# POWER_1_1.net
KiCad netlist of a schematic drawn in Altium Designer
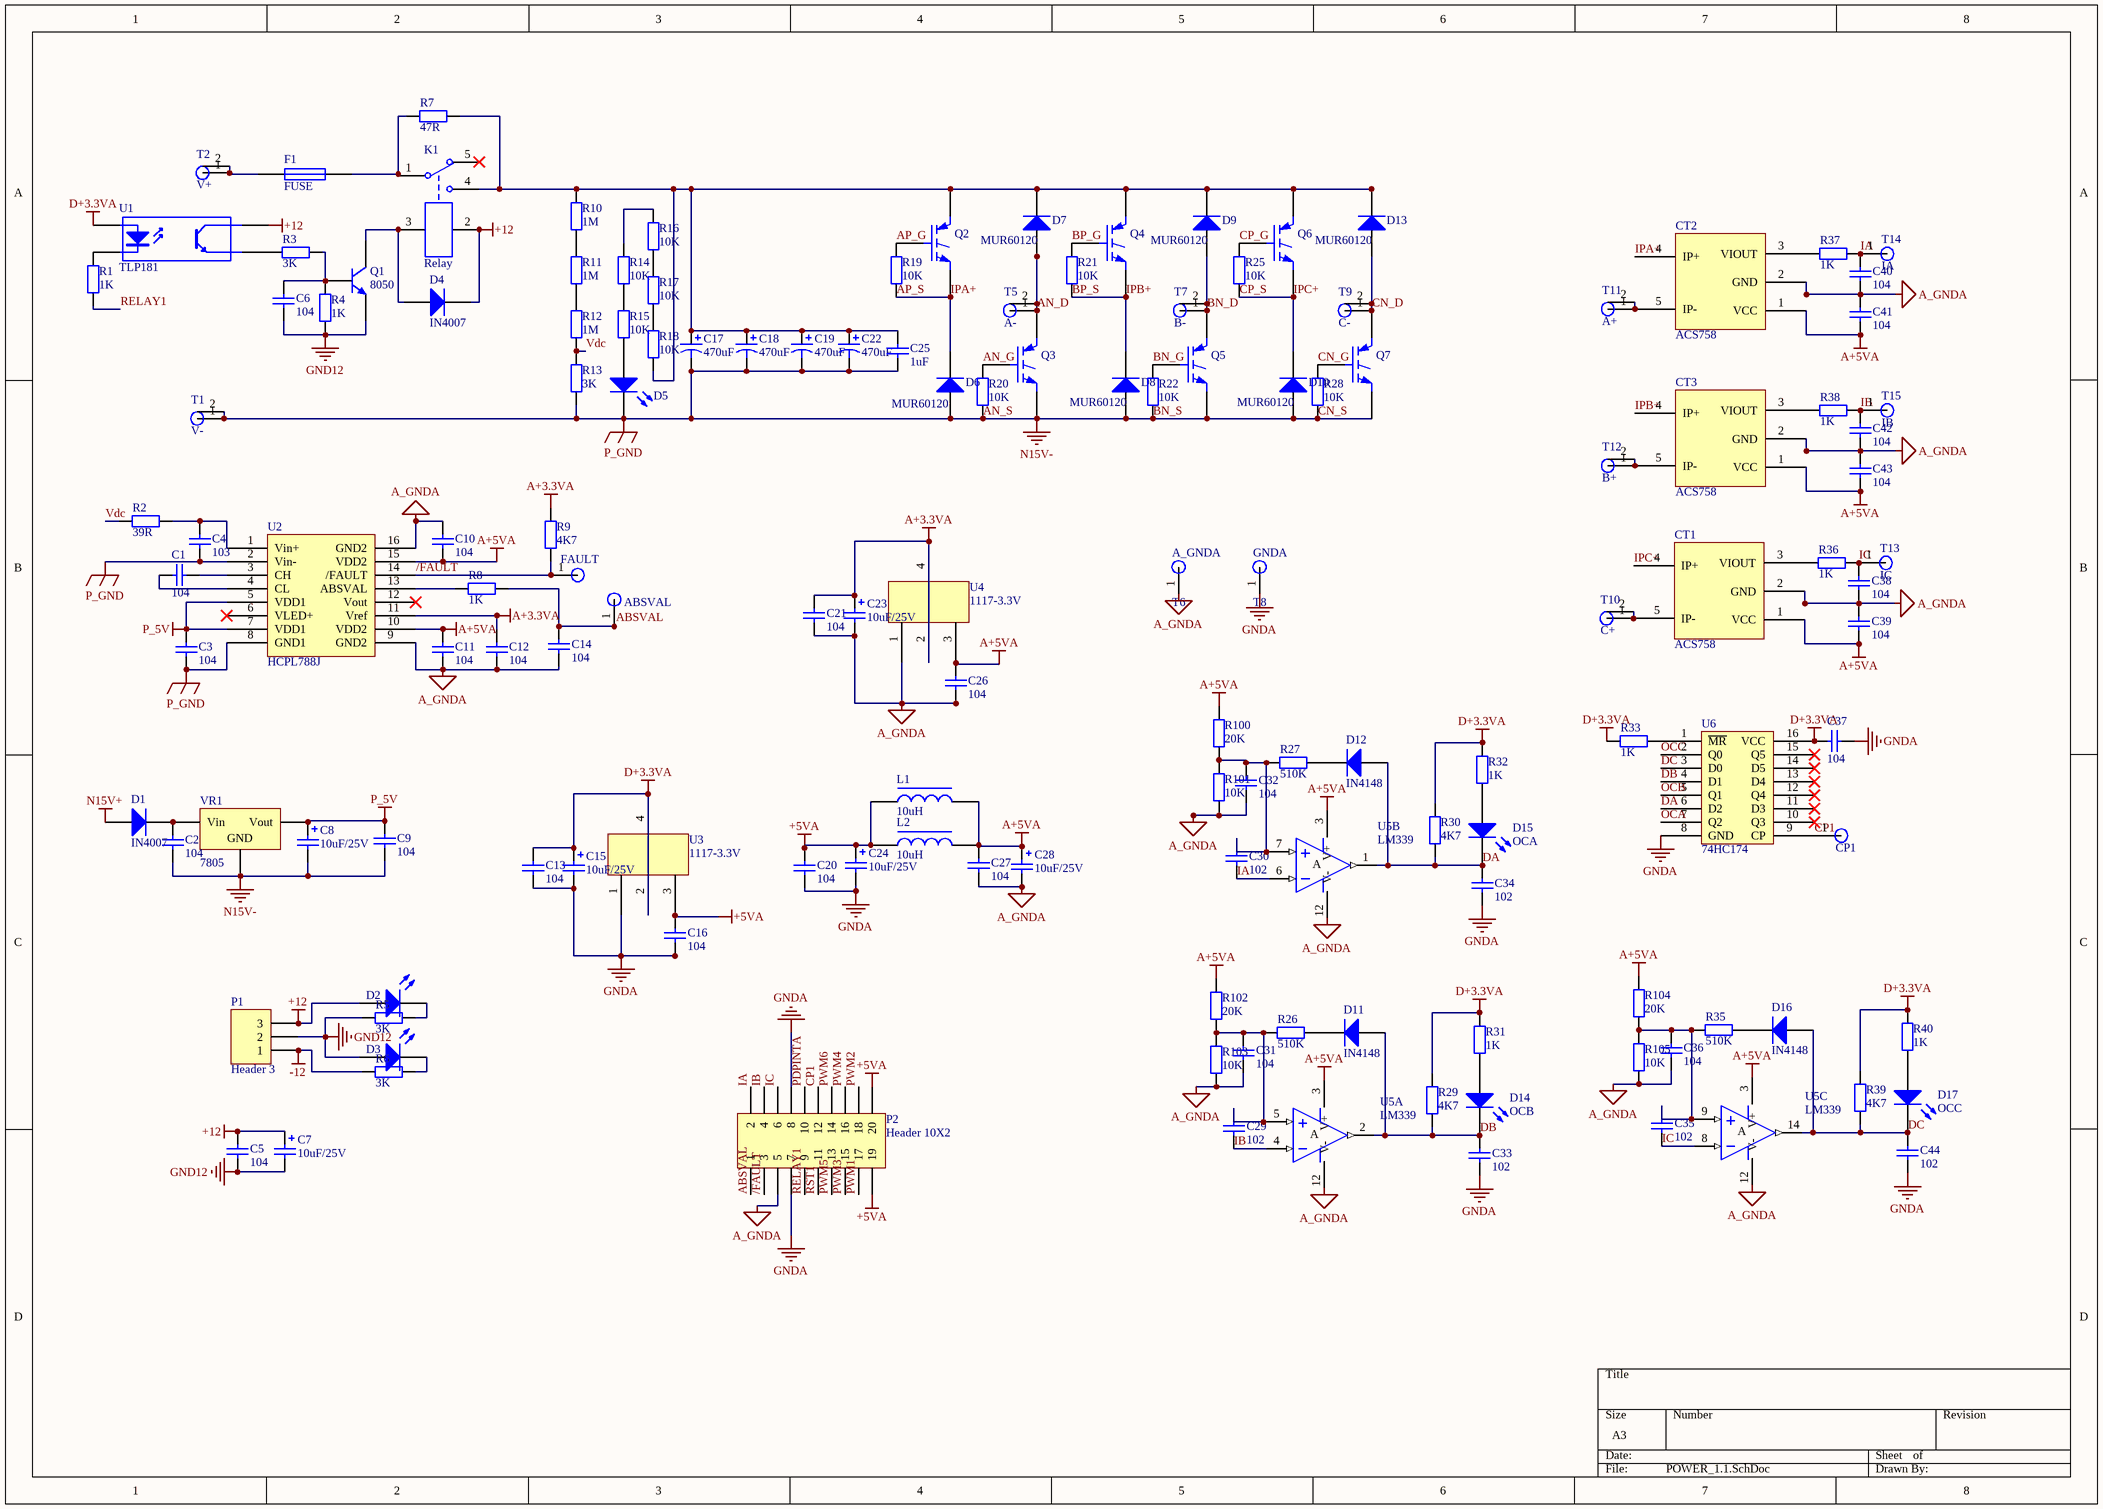
[diagram p0: POWER_1.1.SchDoc]

(export (version "E")
  (design (tool "Eeschema 10.0.6"))
  (components
    (comp (ref "C1")
      (value "104")
      (footprint "C2012-0805")
      (description "普通电容")
      (libsource (lib "*") (part "Cap"))
    )
    (comp (ref "C2")
      (value "104")
      (footprint "C2012-0805")
      (description "普通电容")
      (libsource (lib "*") (part "Cap"))
    )
    (comp (ref "C3")
      (value "104")
      (footprint "C2012-0805")
      (description "普通电容")
      (libsource (lib "*") (part "Cap"))
    )
    (comp (ref "C4")
      (value "103")
      (footprint "C2012-0805")
      (description "普通电容")
      (libsource (lib "*") (part "Cap"))
    )
    (comp (ref "C5")
      (value "104")
      (footprint "C2012-0805")
      (description "普通电容")
      (libsource (lib "*") (part "Cap"))
    )
    (comp (ref "C6")
      (value "104")
      (footprint "C2012-0805")
      (description "普通电容")
      (libsource (lib "Mylib") (part "Cap"))
    )
    (comp (ref "C7")
      (value "10uF/25V")
      (footprint "C_10UF/25V")
      (description "钽电解")
      (libsource (lib "Mylib") (part "Cap tan"))
    )
    (comp (ref "C8")
      (value "10uF/25V")
      (footprint "C_10UF/25V")
      (description "钽电解")
      (libsource (lib "Mylib") (part "Cap tan"))
    )
    (comp (ref "C9")
      (value "104")
      (footprint "C2012-0805")
      (description "普通电容")
      (libsource (lib "*") (part "Cap"))
    )
    (comp (ref "C10")
      (value "104")
      (footprint "C2012-0805")
      (description "普通电容")
      (libsource (lib "*") (part "Cap"))
    )
    (comp (ref "C11")
      (value "104")
      (footprint "C2012-0805")
      (description "普通电容")
      (libsource (lib "*") (part "Cap"))
    )
    (comp (ref "C12")
      (value "104")
      (footprint "C2012-0805")
      (description "普通电容")
      (libsource (lib "*") (part "Cap"))
    )
    (comp (ref "C13")
      (value "104")
      (footprint "C2012-0805")
      (description "普通电容")
      (libsource (lib "*") (part "Cap"))
    )
    (comp (ref "C14")
      (value "104")
      (footprint "C2012-0805")
      (description "普通电容")
      (libsource (lib "*") (part "Cap"))
    )
    (comp (ref "C15")
      (value "10uF/25V")
      (footprint "C_10UF/25V")
      (description "钽电解")
      (libsource (lib "Mylib") (part "Cap tan"))
    )
    (comp (ref "C16")
      (value "104")
      (footprint "C2012-0805")
      (description "普通电容")
      (libsource (lib "*") (part "Cap"))
    )
    (comp (ref "C17")
      (value "470uF")
      (footprint "Rb400mil-450V")
      (description "大电解电容")
      (libsource (lib "Mylib") (part "Cap pol1"))
    )
    (comp (ref "C18")
      (value "470uF")
      (footprint "Rb400mil-450V")
      (description "大电解电容")
      (libsource (lib "Mylib") (part "Cap pol1"))
    )
    (comp (ref "C19")
      (value "470uF")
      (footprint "Rb400mil-450V")
      (description "大电解电容")
      (libsource (lib "Mylib") (part "Cap pol1"))
    )
    (comp (ref "C20")
      (value "104")
      (footprint "C2012-0805")
      (description "普通电容")
      (libsource (lib "*") (part "Cap"))
    )
    (comp (ref "C21")
      (value "104")
      (footprint "C2012-0805")
      (description "普通电容")
      (libsource (lib "*") (part "Cap"))
    )
    (comp (ref "C22")
      (value "470uF")
      (footprint "Rb400mil-450V")
      (description "大电解电容")
      (libsource (lib "Mylib") (part "Cap pol1"))
    )
    (comp (ref "C23")
      (value "10uF/25V")
      (footprint "C_10UF/25V")
      (description "钽电解")
      (libsource (lib "Mylib") (part "Cap tan"))
    )
    (comp (ref "C24")
      (value "10uF/25V")
      (footprint "C_10UF/25V")
      (description "钽电解")
      (libsource (lib "Mylib") (part "Cap tan"))
    )
    (comp (ref "C25")
      (value "1uF")
      (footprint "Rb800mil")
      (description "CBB电容")
      (libsource (lib "Mylib") (part "Cap CBB"))
    )
    (comp (ref "C26")
      (value "104")
      (footprint "C2012-0805")
      (description "普通电容")
      (libsource (lib "*") (part "Cap"))
    )
    (comp (ref "C27")
      (value "104")
      (footprint "C2012-0805")
      (description "普通电容")
      (libsource (lib "*") (part "Cap"))
    )
    (comp (ref "C28")
      (value "10uF/25V")
      (footprint "C_10UF/25V")
      (description "钽电解")
      (libsource (lib "Mylib") (part "Cap tan"))
    )
    (comp (ref "C29")
      (value "102")
      (footprint "C2012-0805")
      (description "普通电容")
      (libsource (lib "*") (part "Cap"))
    )
    (comp (ref "C30")
      (value "102")
      (footprint "C2012-0805")
      (description "普通电容")
      (libsource (lib "*") (part "Cap"))
    )
    (comp (ref "C31")
      (value "104")
      (footprint "C2012-0805")
      (description "普通电容")
      (libsource (lib "*") (part "Cap"))
    )
    (comp (ref "C32")
      (value "104")
      (footprint "C2012-0805")
      (description "普通电容")
      (libsource (lib "*") (part "Cap"))
    )
    (comp (ref "C33")
      (value "102")
      (footprint "C2012-0805")
      (description "普通电容")
      (libsource (lib "*") (part "Cap"))
    )
    (comp (ref "C34")
      (value "102")
      (footprint "C2012-0805")
      (description "普通电容")
      (libsource (lib "*") (part "Cap"))
    )
    (comp (ref "C35")
      (value "102")
      (footprint "C2012-0805")
      (description "普通电容")
      (libsource (lib "*") (part "Cap"))
    )
    (comp (ref "C36")
      (value "104")
      (footprint "C2012-0805")
      (description "普通电容")
      (libsource (lib "*") (part "Cap"))
    )
    (comp (ref "C37")
      (value "104")
      (footprint "C2012-0805")
      (description "普通电容")
      (libsource (lib "*") (part "Cap"))
    )
    (comp (ref "C38")
      (value "104")
      (footprint "C2012-0805")
      (description "普通电容")
      (libsource (lib "Mylib") (part "Cap"))
    )
    (comp (ref "C39")
      (value "104")
      (footprint "C2012-0805")
      (description "普通电容")
      (libsource (lib "Mylib") (part "Cap"))
    )
    (comp (ref "C40")
      (value "104")
      (footprint "C2012-0805")
      (description "普通电容")
      (libsource (lib "Mylib") (part "Cap"))
    )
    (comp (ref "C41")
      (value "104")
      (footprint "C2012-0805")
      (description "普通电容")
      (libsource (lib "Mylib") (part "Cap"))
    )
    (comp (ref "C42")
      (value "104")
      (footprint "C2012-0805")
      (description "普通电容")
      (libsource (lib "Mylib") (part "Cap"))
    )
    (comp (ref "C43")
      (value "104")
      (footprint "C2012-0805")
      (description "普通电容")
      (libsource (lib "Mylib") (part "Cap"))
    )
    (comp (ref "C44")
      (value "102")
      (footprint "C2012-0805")
      (description "普通电容")
      (libsource (lib "*") (part "Cap"))
    )
    (comp (ref "CT1")
      (value "ACS758")
      (footprint "ACS758-LCB-050U-PFF")
      (libsource (lib "Mylib") (part "ACS758"))
    )
    (comp (ref "CT2")
      (value "ACS758")
      (footprint "ACS758-LCB-050U-PFF")
      (libsource (lib "Mylib") (part "ACS758"))
    )
    (comp (ref "CT3")
      (value "ACS758")
      (footprint "ACS758-LCB-050U-PFF")
      (libsource (lib "Mylib") (part "ACS758"))
    )
    (comp (ref "D1")
      (value "IN4007")
      (footprint "DIODE4007")
      (description "普通整流二极管")
      (libsource (lib "Mylib") (part "Diode IN4007"))
    )
    (comp (ref "D2") (value "~") (footprint "LED-SMD") (libsource (lib "Mylib") (part "LED")))
    (comp (ref "D3") (value "~") (footprint "LED-SMD") (libsource (lib "Mylib") (part "LED")))
    (comp (ref "D4")
      (value "IN4007")
      (footprint "DIODE4007")
      (description "普通整流二极管")
      (libsource (lib "Mylib") (part "Diode IN4007"))
    )
    (comp (ref "D5") (value "LED") (footprint "LED-SMD") (libsource (lib "Mylib") (part "LED")))
    (comp (ref "D6")
      (value "MUR60120")
      (footprint "DIO40A1200V")
      (libsource (lib "Mylib") (part "Diode HFA08TB60"))
    )
    (comp (ref "D7")
      (value "MUR60120")
      (footprint "DIO40A1200V")
      (libsource (lib "Mylib") (part "Diode HFA08TB60"))
    )
    (comp (ref "D8")
      (value "MUR60120")
      (footprint "DIO40A1200V")
      (libsource (lib "Mylib") (part "Diode HFA08TB60"))
    )
    (comp (ref "D9")
      (value "MUR60120")
      (footprint "DIO40A1200V")
      (libsource (lib "Mylib") (part "Diode HFA08TB60"))
    )
    (comp (ref "D10")
      (value "MUR60120")
      (footprint "DIO40A1200V")
      (libsource (lib "Mylib") (part "Diode HFA08TB60"))
    )
    (comp (ref "D11")
      (value "IN4148")
      (footprint "IN4148")
      (description "开关二极管")
      (libsource (lib "*") (part "Diode IN4148"))
    )
    (comp (ref "D12")
      (value "IN4148")
      (footprint "IN4148")
      (description "开关二极管")
      (libsource (lib "*") (part "Diode IN4148"))
    )
    (comp (ref "D13")
      (value "MUR60120")
      (footprint "DIO40A1200V")
      (libsource (lib "Mylib") (part "Diode HFA08TB60"))
    )
    (comp (ref "D14") (value "OCB") (footprint "LED-SMD") (libsource (lib "Mylib") (part "LED")))
    (comp (ref "D15") (value "OCA") (footprint "LED-SMD") (libsource (lib "Mylib") (part "LED")))
    (comp (ref "D16")
      (value "IN4148")
      (footprint "IN4148")
      (description "开关二极管")
      (libsource (lib "*") (part "Diode IN4148"))
    )
    (comp (ref "D17") (value "OCC") (footprint "LED-SMD") (libsource (lib "Mylib") (part "LED")))
    (comp (ref "F1") (value "FUSE") (footprint "FUSE") (libsource (lib "Mylib") (part "FUSE")))
    (comp (ref "K1") (value "Relay") (footprint "Relay(30A)") (libsource (lib "Mylib") (part "Relay(30A)")))
    (comp (ref "L1") (value "10uH") (footprint "R2012-0805") (libsource (lib "*") (part "Inductor")))
    (comp (ref "L2") (value "10uH") (footprint "R2012-0805") (libsource (lib "*") (part "Inductor")))
    (comp (ref "P1")
      (value "Header 3")
      (footprint "HDR1X3")
      (description "Header, 3-Pin")
      (fields (field (name "PUBLISHER") "Altium Limited"))
      (libsource (lib "Miscellaneous Connectors") (part "Header 3"))
    )
    (comp (ref "P2")
      (value "Header 10X2")
      (footprint "HDR2X10")
      (description "Header, 10-Pin, Dual row")
      (fields (field (name "PUBLISHER") "Altium Limited"))
      (libsource (lib "Miscellaneous Connectors") (part "Header 10X2"))
    )
    (comp (ref "Q1") (value "8050") (footprint "NPN8050") (libsource (lib "Mylib") (part "NPN8050")))
    (comp (ref "Q2") (value "~") (footprint "IGBT TO247 40A 1200V") (libsource (lib "Mylib") (part "IGBT-N")))
    (comp (ref "Q3") (value "~") (footprint "IGBT TO247 40A 1200V") (libsource (lib "Mylib") (part "IGBT-N")))
    (comp (ref "Q4") (value "~") (footprint "IGBT TO247 40A 1200V") (libsource (lib "Mylib") (part "IGBT-N")))
    (comp (ref "Q5") (value "~") (footprint "IGBT TO247 40A 1200V") (libsource (lib "Mylib") (part "IGBT-N")))
    (comp (ref "Q6") (value "~") (footprint "IGBT TO247 40A 1200V") (libsource (lib "Mylib") (part "IGBT-N")))
    (comp (ref "Q7") (value "~") (footprint "IGBT TO247 40A 1200V") (libsource (lib "Mylib") (part "IGBT-N")))
    (comp (ref "R1") (value "1K") (footprint "R2012-0805") (libsource (lib "") (part "Res_3")))
    (comp (ref "R2") (value "39R") (footprint "R2012-0805") (libsource (lib "") (part "Res_3")))
    (comp (ref "R3") (value "3K") (footprint "R2012-0805") (libsource (lib "") (part "Res_2")))
    (comp (ref "R4") (value "1K") (footprint "R2012-0805") (libsource (lib "Mylib") (part "Res")))
    (comp (ref "R5") (value "3K") (footprint "R2012-0805") (libsource (lib "") (part "Res_3")))
    (comp (ref "R6") (value "3K") (footprint "R2012-0805") (libsource (lib "") (part "Res_3")))
    (comp (ref "R7") (value "47R") (footprint "AXIAL-1*1.3") (libsource (lib "") (part "Res_2")))
    (comp (ref "R8") (value "1K") (footprint "R2012-0805") (libsource (lib "") (part "Res_3")))
    (comp (ref "R9") (value "4K7") (footprint "R2012-0805") (libsource (lib "") (part "Res_2")))
    (comp (ref "R10") (value "1M") (footprint "R2012-0805") (libsource (lib "Mylib") (part "Res")))
    (comp (ref "R11") (value "1M") (footprint "R2012-0805") (libsource (lib "Mylib") (part "Res")))
    (comp (ref "R12") (value "1M") (footprint "R2012-0805") (libsource (lib "Mylib") (part "Res")))
    (comp (ref "R13") (value "3K") (footprint "R2012-0805") (libsource (lib "Mylib") (part "Res")))
    (comp (ref "R14") (value "10K") (footprint "R2012-0805") (libsource (lib "Mylib") (part "Res")))
    (comp (ref "R15") (value "10K") (footprint "R2012-0805") (libsource (lib "Mylib") (part "Res")))
    (comp (ref "R16") (value "10K") (footprint "R2012-0805") (libsource (lib "Mylib") (part "Res")))
    (comp (ref "R17") (value "10K") (footprint "R2012-0805") (libsource (lib "Mylib") (part "Res")))
    (comp (ref "R18") (value "10K") (footprint "R2012-0805") (libsource (lib "Mylib") (part "Res")))
    (comp (ref "R19") (value "10K") (footprint "R2012-0805") (libsource (lib "Mylib") (part "Res")))
    (comp (ref "R20") (value "10K") (footprint "R2012-0805") (libsource (lib "Mylib") (part "Res")))
    (comp (ref "R21") (value "10K") (footprint "R2012-0805") (libsource (lib "Mylib") (part "Res")))
    (comp (ref "R22") (value "10K") (footprint "R2012-0805") (libsource (lib "Mylib") (part "Res")))
    (comp (ref "R25") (value "10K") (footprint "R2012-0805") (libsource (lib "Mylib") (part "Res")))
    (comp (ref "R26") (value "510K") (footprint "R2012-0805") (libsource (lib "*") (part "Res")))
    (comp (ref "R27") (value "510K") (footprint "R2012-0805") (libsource (lib "*") (part "Res")))
    (comp (ref "R28") (value "10K") (footprint "R2012-0805") (libsource (lib "Mylib") (part "Res")))
    (comp (ref "R29") (value "4K7") (footprint "R2012-0805") (libsource (lib "") (part "Res_2")))
    (comp (ref "R30") (value "4K7") (footprint "R2012-0805") (libsource (lib "") (part "Res_2")))
    (comp (ref "R31") (value "1K") (footprint "R2012-0805") (libsource (lib "") (part "Res_2")))
    (comp (ref "R32") (value "1K") (footprint "R2012-0805") (libsource (lib "") (part "Res_2")))
    (comp (ref "R33") (value "1K") (footprint "R2012-0805") (libsource (lib "*") (part "Res")))
    (comp (ref "R35") (value "510K") (footprint "R2012-0805") (libsource (lib "*") (part "Res")))
    (comp (ref "R36") (value "1K") (footprint "R2012-0805") (libsource (lib "") (part "Res_1")))
    (comp (ref "R37") (value "1K") (footprint "R2012-0805") (libsource (lib "") (part "Res_1")))
    (comp (ref "R38") (value "1K") (footprint "R2012-0805") (libsource (lib "") (part "Res_1")))
    (comp (ref "R39") (value "4K7") (footprint "R2012-0805") (libsource (lib "") (part "Res_2")))
    (comp (ref "R40") (value "1K") (footprint "R2012-0805") (libsource (lib "") (part "Res_2")))
    (comp (ref "R100") (value "20K") (footprint "R2012-0805") (libsource (lib "") (part "Res_1")))
    (comp (ref "R101") (value "10K") (footprint "R2012-0805") (libsource (lib "") (part "Res_1")))
    (comp (ref "R102") (value "20K") (footprint "R2012-0805") (libsource (lib "") (part "Res_1")))
    (comp (ref "R103") (value "10K") (footprint "R2012-0805") (libsource (lib "") (part "Res_1")))
    (comp (ref "R104") (value "20K") (footprint "R2012-0805") (libsource (lib "") (part "Res_1")))
    (comp (ref "R105") (value "10K") (footprint "R2012-0805") (libsource (lib "") (part "Res_1")))
    (comp (ref "T1")
      (value "V-")
      (footprint "TEM")
      (description "电源端子")
      (libsource (lib "Mylib") (part "TEM"))
    )
    (comp (ref "T2")
      (value "V+")
      (footprint "TEM")
      (description "电源端子")
      (libsource (lib "Mylib") (part "TEM"))
    )
    (comp (ref "T3") (value "FAULT") (footprint "PIN1") (description "测试脚") (libsource (lib "*") (part "TP")))
    (comp (ref "T4")
      (value "ABSVAL")
      (footprint "PIN1")
      (description "测试脚")
      (libsource (lib "*") (part "TP"))
    )
    (comp (ref "T5")
      (value "A-")
      (footprint "TEM")
      (description "电源端子")
      (libsource (lib "Mylib") (part "TEM"))
    )
    (comp (ref "T6")
      (value "A_GNDA")
      (footprint "PIN1")
      (description "测试脚")
      (libsource (lib "Mylib") (part "TP"))
    )
    (comp (ref "T7")
      (value "B-")
      (footprint "TEM")
      (description "电源端子")
      (libsource (lib "Mylib") (part "TEM"))
    )
    (comp (ref "T8")
      (value "GNDA")
      (footprint "PIN1")
      (description "测试脚")
      (libsource (lib "Mylib") (part "TP"))
    )
    (comp (ref "T9")
      (value "C-")
      (footprint "TEM")
      (description "电源端子")
      (libsource (lib "Mylib") (part "TEM"))
    )
    (comp (ref "T10")
      (value "C+")
      (footprint "TEM")
      (description "电源端子")
      (libsource (lib "Mylib") (part "TEM"))
    )
    (comp (ref "T11")
      (value "A+")
      (footprint "TEM")
      (description "电源端子")
      (libsource (lib "Mylib") (part "TEM"))
    )
    (comp (ref "T12")
      (value "B+")
      (footprint "TEM")
      (description "电源端子")
      (libsource (lib "Mylib") (part "TEM"))
    )
    (comp (ref "T13") (value "IC") (footprint "PIN1") (description "测试脚") (libsource (lib "*") (part "TP")))
    (comp (ref "T14") (value "IA") (footprint "PIN1") (description "测试脚") (libsource (lib "*") (part "TP")))
    (comp (ref "T15") (value "IB") (footprint "PIN1") (description "测试脚") (libsource (lib "*") (part "TP")))
    (comp (ref "TP1")
      (value "CP1")
      (footprint "PIN1")
      (description "测试脚")
      (libsource (lib "Mylib") (part "TP"))
    )
    (comp (ref "U1") (value "TLP181") (footprint "TLP181") (libsource (lib "Mylib") (part "TLP181")))
    (comp (ref "U2") (value "HCPL788J") (footprint "HCPL788J") (libsource (lib "*") (part "HCPL788J")))
    (comp (ref "U3") (value "1117-3.3V") (footprint "1117-3.3V") (libsource (lib "Mylib") (part "1117")))
    (comp (ref "U4") (value "1117-3.3V") (footprint "1117-3.3V") (libsource (lib "Mylib") (part "1117")))
    (comp (ref "U5") (value "LM339") (footprint "LM339") (libsource (lib "Mylib") (part "LM339")))
    (comp (ref "U6")
      (value "74HC174")
      (footprint "74HC174")
      (description "带公共时钟和复位六D触发器")
      (libsource (lib "Mylib") (part "74HC174"))
    )
    (comp (ref "VR1")
      (value "7805")
      (footprint "MC78L05")
      (description "三端稳压")
      (libsource (lib "Mylib") (part "VR78"))
    )
  )
  (nets
    (net (code "1") (name "+5VA") (class "Default")
      (node (ref "C16") (pin "2") (pinfunction "2_2") (pintype "passive"))
      (node (ref "C20") (pin "2") (pinfunction "2_2") (pintype "passive"))
      (node (ref "C24") (pin "1") (pinfunction "1_1") (pintype "passive"))
      (node (ref "L1") (pin "1") (pinfunction "1_1") (pintype "passive"))
      (node (ref "L2") (pin "1") (pinfunction "1_1") (pintype "passive"))
      (node (ref "P2") (pin "19") (pinfunction "19_19") (pintype "passive"))
      (node (ref "P2") (pin "20") (pinfunction "20_20") (pintype "passive"))
      (node (ref "U3") (pin "3") (pintype "passive"))
    )
    (net (code "2") (name "+12") (class "Default")
      (node (ref "C5") (pin "1") (pinfunction "1_1") (pintype "passive"))
      (node (ref "C7") (pin "1") (pinfunction "1_1") (pintype "passive"))
      (node (ref "D2") (pin "1") (pinfunction "A_1") (pintype "passive"))
      (node (ref "D4") (pin "2") (pinfunction "K_2") (pintype "passive"))
      (node (ref "K1") (pin "2") (pinfunction "2_2") (pintype "passive"))
      (node (ref "P1") (pin "3") (pinfunction "3_3") (pintype "passive"))
      (node (ref "U1") (pin "6") (pinfunction "C_6") (pintype "passive"))
    )
    (net (code "3") (name "-12") (class "Default")
      (node (ref "P1") (pin "1") (pinfunction "1_1") (pintype "passive"))
      (node (ref "R6") (pin "1") (pinfunction "1_1") (pintype "passive"))
    )
    (net (code "4") (name "/ABSVAL") (class "Default")
      (node (ref "C14") (pin "2") (pinfunction "2_2") (pintype "passive"))
      (node (ref "P2") (pin "1") (pinfunction "1_1") (pintype "passive"))
      (node (ref "R8") (pin "2") (pinfunction "2_2") (pintype "passive"))
      (node (ref "T4") (pin "1") (pinfunction "A_1") (pintype "passive"))
    )
    (net (code "5") (name "/AN_D") (class "Default")
      (node (ref "D7") (pin "3") (pinfunction "A_3") (pintype "passive"))
      (node (ref "Q3") (pin "2") (pinfunction "C_2") (pintype "passive"))
      (node (ref "T5") (pin "1") (pinfunction "A_1") (pintype "passive"))
      (node (ref "T5") (pin "2") (pinfunction "2_2") (pintype "passive"))
    )
    (net (code "6") (name "/AN_G") (class "Default")
      (node (ref "Q3") (pin "1") (pinfunction "G_1") (pintype "passive"))
      (node (ref "R20") (pin "2") (pinfunction "2_2") (pintype "passive"))
    )
    (net (code "7") (name "/AP_G") (class "Default")
      (node (ref "Q2") (pin "1") (pinfunction "G_1") (pintype "passive"))
      (node (ref "R19") (pin "2") (pinfunction "2_2") (pintype "passive"))
    )
    (net (code "8") (name "/AP_S") (class "Default")
      (node (ref "CT2") (pin "4") (pinfunction "IP+_4") (pintype "passive"))
      (node (ref "D6") (pin "1") (pinfunction "K_1") (pintype "passive"))
      (node (ref "Q2") (pin "3") (pinfunction "E_3") (pintype "passive"))
      (node (ref "R19") (pin "1") (pinfunction "1_1") (pintype "passive"))
    )
    (net (code "9") (name "/BN_D") (class "Default")
      (node (ref "D9") (pin "3") (pinfunction "A_3") (pintype "passive"))
      (node (ref "Q5") (pin "2") (pinfunction "C_2") (pintype "passive"))
      (node (ref "T7") (pin "1") (pinfunction "A_1") (pintype "passive"))
      (node (ref "T7") (pin "2") (pinfunction "2_2") (pintype "passive"))
    )
    (net (code "10") (name "/BN_G") (class "Default")
      (node (ref "Q5") (pin "1") (pinfunction "G_1") (pintype "passive"))
      (node (ref "R22") (pin "2") (pinfunction "2_2") (pintype "passive"))
    )
    (net (code "11") (name "/BP_G") (class "Default")
      (node (ref "Q4") (pin "1") (pinfunction "G_1") (pintype "passive"))
      (node (ref "R21") (pin "2") (pinfunction "2_2") (pintype "passive"))
    )
    (net (code "12") (name "/BP_S") (class "Default")
      (node (ref "CT3") (pin "4") (pinfunction "IP+_4") (pintype "passive"))
      (node (ref "D8") (pin "1") (pinfunction "K_1") (pintype "passive"))
      (node (ref "Q4") (pin "3") (pinfunction "E_3") (pintype "passive"))
      (node (ref "R21") (pin "1") (pinfunction "1_1") (pintype "passive"))
    )
    (net (code "13") (name "/CN_D") (class "Default")
      (node (ref "D13") (pin "3") (pinfunction "A_3") (pintype "passive"))
      (node (ref "Q7") (pin "2") (pinfunction "C_2") (pintype "passive"))
      (node (ref "T9") (pin "1") (pinfunction "A_1") (pintype "passive"))
      (node (ref "T9") (pin "2") (pinfunction "2_2") (pintype "passive"))
    )
    (net (code "14") (name "/CN_G") (class "Default")
      (node (ref "Q7") (pin "1") (pinfunction "G_1") (pintype "passive"))
      (node (ref "R28") (pin "2") (pinfunction "2_2") (pintype "passive"))
    )
    (net (code "15") (name "/CP1") (class "Default")
      (node (ref "P2") (pin "12") (pinfunction "12_12") (pintype "passive"))
      (node (ref "TP1") (pin "1") (pinfunction "A_1") (pintype "passive"))
      (node (ref "U6") (pin "9") (pinfunction "CP_9") (pintype "passive"))
    )
    (net (code "16") (name "/CP_G") (class "Default")
      (node (ref "Q6") (pin "1") (pinfunction "G_1") (pintype "passive"))
      (node (ref "R25") (pin "2") (pinfunction "2_2") (pintype "passive"))
    )
    (net (code "17") (name "/CP_S") (class "Default")
      (node (ref "CT1") (pin "4") (pinfunction "IP+_4") (pintype "passive"))
      (node (ref "D10") (pin "1") (pinfunction "K_1") (pintype "passive"))
      (node (ref "Q6") (pin "3") (pinfunction "E_3") (pintype "passive"))
      (node (ref "R25") (pin "1") (pinfunction "1_1") (pintype "passive"))
    )
    (net (code "18") (name "/DA") (class "Default")
      (node (ref "C34") (pin "2") (pinfunction "2_2") (pintype "passive"))
      (node (ref "D12") (pin "1") (pinfunction "A_1") (pintype "passive"))
      (node (ref "D15") (pin "2") (pinfunction "K_2") (pintype "passive"))
      (node (ref "R30") (pin "1") (pinfunction "1_1") (pintype "passive"))
      (node (ref "U5") (pin "1") (pinfunction "OUT_1") (pintype "output"))
      (node (ref "U6") (pin "6") (pinfunction "D2_6") (pintype "passive"))
    )
    (net (code "19") (name "/DB") (class "Default")
      (node (ref "C33") (pin "2") (pinfunction "2_2") (pintype "passive"))
      (node (ref "D11") (pin "1") (pinfunction "A_1") (pintype "passive"))
      (node (ref "D14") (pin "2") (pinfunction "K_2") (pintype "passive"))
      (node (ref "R29") (pin "1") (pinfunction "1_1") (pintype "passive"))
      (node (ref "U5") (pin "2") (pinfunction "OUT_2") (pintype "output"))
      (node (ref "U6") (pin "4") (pinfunction "D1_4") (pintype "passive"))
    )
    (net (code "20") (name "/DC") (class "Default")
      (node (ref "C44") (pin "2") (pinfunction "2_2") (pintype "passive"))
      (node (ref "D16") (pin "1") (pinfunction "A_1") (pintype "passive"))
      (node (ref "D17") (pin "2") (pinfunction "K_2") (pintype "passive"))
      (node (ref "R39") (pin "1") (pinfunction "1_1") (pintype "passive"))
      (node (ref "U5") (pin "14") (pinfunction "OUT_14") (pintype "output"))
      (node (ref "U6") (pin "3") (pinfunction "D0_3") (pintype "passive"))
    )
    (net (code "21") (name "/IA") (class "Default")
      (node (ref "C30") (pin "1") (pinfunction "1_1") (pintype "passive"))
      (node (ref "C40") (pin "2") (pinfunction "2_2") (pintype "passive"))
      (node (ref "P2") (pin "2") (pinfunction "2_2") (pintype "passive"))
      (node (ref "R37") (pin "2") (pinfunction "2_2") (pintype "passive"))
      (node (ref "T14") (pin "1") (pinfunction "A_1") (pintype "passive"))
      (node (ref "U5") (pin "6") (pinfunction "IN+_6") (pintype "input"))
    )
    (net (code "22") (name "/IB") (class "Default")
      (node (ref "C29") (pin "1") (pinfunction "1_1") (pintype "passive"))
      (node (ref "C42") (pin "2") (pinfunction "2_2") (pintype "passive"))
      (node (ref "P2") (pin "4") (pinfunction "4_4") (pintype "passive"))
      (node (ref "R38") (pin "2") (pinfunction "2_2") (pintype "passive"))
      (node (ref "T15") (pin "1") (pinfunction "A_1") (pintype "passive"))
      (node (ref "U5") (pin "4") (pinfunction "IN+_4") (pintype "input"))
    )
    (net (code "23") (name "/IC") (class "Default")
      (node (ref "C35") (pin "1") (pinfunction "1_1") (pintype "passive"))
      (node (ref "C38") (pin "2") (pinfunction "2_2") (pintype "passive"))
      (node (ref "P2") (pin "6") (pinfunction "6_6") (pintype "passive"))
      (node (ref "R36") (pin "2") (pinfunction "2_2") (pintype "passive"))
      (node (ref "T13") (pin "1") (pinfunction "A_1") (pintype "passive"))
      (node (ref "U5") (pin "8") (pinfunction "IN+_8") (pintype "input"))
    )
    (net (code "24") (name "/OCA") (class "Default")
      (node (ref "U6") (pin "7") (pinfunction "Q2_7") (pintype "passive"))
    )
    (net (code "25") (name "/OCB") (class "Default")
      (node (ref "U6") (pin "5") (pinfunction "Q1_5") (pintype "passive"))
    )
    (net (code "26") (name "/OCC") (class "Default")
      (node (ref "U6") (pin "2") (pinfunction "Q0_2") (pintype "passive"))
    )
    (net (code "27") (name "/PDPINTA") (class "Default")
      (node (ref "P2") (pin "10") (pinfunction "10_10") (pintype "passive"))
    )
    (net (code "28") (name "/PWM1") (class "Default")
      (node (ref "P2") (pin "17") (pinfunction "17_17") (pintype "passive"))
    )
    (net (code "29") (name "/PWM2") (class "Default")
      (node (ref "P2") (pin "18") (pinfunction "18_18") (pintype "passive"))
    )
    (net (code "30") (name "/PWM3") (class "Default")
      (node (ref "P2") (pin "15") (pinfunction "15_15") (pintype "passive"))
    )
    (net (code "31") (name "/PWM4") (class "Default")
      (node (ref "P2") (pin "16") (pinfunction "16_16") (pintype "passive"))
    )
    (net (code "32") (name "/PWM5") (class "Default")
      (node (ref "P2") (pin "13") (pinfunction "13_13") (pintype "passive"))
    )
    (net (code "33") (name "/PWM6") (class "Default")
      (node (ref "P2") (pin "14") (pinfunction "14_14") (pintype "passive"))
    )
    (net (code "34") (name "/RELAY1") (class "Default")
      (node (ref "P2") (pin "9") (pinfunction "9_9") (pintype "passive"))
      (node (ref "R1") (pin "2") (pinfunction "2_2") (pintype "passive"))
    )
    (net (code "35") (name "/RST1") (class "Default")
      (node (ref "P2") (pin "11") (pinfunction "11_11") (pintype "passive"))
    )
    (net (code "36") (name "/Vdc") (class "Default")
      (node (ref "R12") (pin "1") (pinfunction "1_1") (pintype "passive"))
      (node (ref "R13") (pin "2") (pinfunction "2_2") (pintype "passive"))
      (node (ref "R2") (pin "1") (pinfunction "1_1") (pintype "passive"))
    )
    (net (code "37") (name "/{slash}FAULT") (class "Default")
      (node (ref "P2") (pin "3") (pinfunction "3_3") (pintype "passive"))
      (node (ref "R9") (pin "1") (pinfunction "1_1") (pintype "passive"))
      (node (ref "T3") (pin "1") (pinfunction "A_1") (pintype "passive"))
      (node (ref "U2") (pin "14") (pinfunction "/FAULT_14") (pintype "passive"))
    )
    (net (code "38") (name "A+3.3VA") (class "Default")
      (node (ref "C12") (pin "2") (pinfunction "2_2") (pintype "passive"))
      (node (ref "C21") (pin "2") (pinfunction "2_2") (pintype "passive"))
      (node (ref "C23") (pin "1") (pinfunction "1_1") (pintype "passive"))
      (node (ref "R9") (pin "2") (pinfunction "2_2") (pintype "passive"))
      (node (ref "U2") (pin "11") (pinfunction "Vref_11") (pintype "passive"))
      (node (ref "U4") (pin "2") (pintype "passive"))
      (node (ref "U4") (pin "4") (pintype "passive"))
    )
    (net (code "39") (name "A+5VA") (class "Default")
      (node (ref "C10") (pin "1") (pinfunction "1_1") (pintype "passive"))
      (node (ref "C11") (pin "2") (pinfunction "2_2") (pintype "passive"))
      (node (ref "C26") (pin "2") (pinfunction "2_2") (pintype "passive"))
      (node (ref "C27") (pin "2") (pinfunction "2_2") (pintype "passive"))
      (node (ref "C28") (pin "1") (pinfunction "1_1") (pintype "passive"))
      (node (ref "C39") (pin "1") (pinfunction "1_1") (pintype "passive"))
      (node (ref "C41") (pin "1") (pinfunction "1_1") (pintype "passive"))
      (node (ref "C43") (pin "1") (pinfunction "1_1") (pintype "passive"))
      (node (ref "CT1") (pin "1") (pinfunction "VCC_1") (pintype "passive"))
      (node (ref "CT2") (pin "1") (pinfunction "VCC_1") (pintype "passive"))
      (node (ref "CT3") (pin "1") (pinfunction "VCC_1") (pintype "passive"))
      (node (ref "L1") (pin "2") (pinfunction "2_2") (pintype "passive"))
      (node (ref "L2") (pin "2") (pinfunction "2_2") (pintype "passive"))
      (node (ref "R100") (pin "1") (pinfunction "1_1") (pintype "passive"))
      (node (ref "R102") (pin "1") (pinfunction "1_1") (pintype "passive"))
      (node (ref "R104") (pin "1") (pinfunction "1_1") (pintype "passive"))
      (node (ref "U2") (pin "10") (pinfunction "VDD2_10") (pintype "passive"))
      (node (ref "U2") (pin "15") (pinfunction "VDD2_15") (pintype "passive"))
      (node (ref "U4") (pin "3") (pintype "passive"))
      (node (ref "U5") (pin "3") (pinfunction "V+_3") (pintype "power_in"))
    )
    (net (code "40") (name "A_GNDA") (class "Default")
      (node (ref "C10") (pin "2") (pinfunction "2_2") (pintype "passive"))
      (node (ref "C11") (pin "1") (pinfunction "1_1") (pintype "passive"))
      (node (ref "C12") (pin "1") (pinfunction "1_1") (pintype "passive"))
      (node (ref "C14") (pin "1") (pinfunction "1_1") (pintype "passive"))
      (node (ref "C21") (pin "1") (pinfunction "1_1") (pintype "passive"))
      (node (ref "C23") (pin "2") (pinfunction "2_2") (pintype "passive"))
      (node (ref "C26") (pin "1") (pinfunction "1_1") (pintype "passive"))
      (node (ref "C27") (pin "1") (pinfunction "1_1") (pintype "passive"))
      (node (ref "C28") (pin "2") (pinfunction "2_2") (pintype "passive"))
      (node (ref "C31") (pin "1") (pinfunction "1_1") (pintype "passive"))
      (node (ref "C32") (pin "1") (pinfunction "1_1") (pintype "passive"))
      (node (ref "C36") (pin "1") (pinfunction "1_1") (pintype "passive"))
      (node (ref "C38") (pin "1") (pinfunction "1_1") (pintype "passive"))
      (node (ref "C39") (pin "2") (pinfunction "2_2") (pintype "passive"))
      (node (ref "C40") (pin "1") (pinfunction "1_1") (pintype "passive"))
      (node (ref "C41") (pin "2") (pinfunction "2_2") (pintype "passive"))
      (node (ref "C42") (pin "1") (pinfunction "1_1") (pintype "passive"))
      (node (ref "C43") (pin "2") (pinfunction "2_2") (pintype "passive"))
      (node (ref "CT1") (pin "2") (pinfunction "GND_2") (pintype "passive"))
      (node (ref "CT2") (pin "2") (pinfunction "GND_2") (pintype "passive"))
      (node (ref "CT3") (pin "2") (pinfunction "GND_2") (pintype "passive"))
      (node (ref "P2") (pin "5") (pinfunction "5_5") (pintype "passive"))
      (node (ref "R101") (pin "2") (pinfunction "2_2") (pintype "passive"))
      (node (ref "R103") (pin "2") (pinfunction "2_2") (pintype "passive"))
      (node (ref "R105") (pin "2") (pinfunction "2_2") (pintype "passive"))
      (node (ref "T6") (pin "1") (pinfunction "A_1") (pintype "passive"))
      (node (ref "U2") (pin "16") (pinfunction "GND2_16") (pintype "passive"))
      (node (ref "U2") (pin "9") (pinfunction "GND2_9") (pintype "passive"))
      (node (ref "U4") (pin "1") (pintype "passive"))
      (node (ref "U5") (pin "12") (pinfunction "V-_12") (pintype "power_in"))
    )
    (net (code "41") (name "D+3.3VA") (class "Default")
      (node (ref "C13") (pin "2") (pinfunction "2_2") (pintype "passive"))
      (node (ref "C15") (pin "1") (pinfunction "1_1") (pintype "passive"))
      (node (ref "C37") (pin "2") (pinfunction "2_2") (pintype "passive"))
      (node (ref "R29") (pin "2") (pinfunction "2_2") (pintype "passive"))
      (node (ref "R30") (pin "2") (pinfunction "2_2") (pintype "passive"))
      (node (ref "R31") (pin "2") (pinfunction "2_2") (pintype "passive"))
      (node (ref "R32") (pin "2") (pinfunction "2_2") (pintype "passive"))
      (node (ref "R33") (pin "2") (pinfunction "2_2") (pintype "passive"))
      (node (ref "R39") (pin "2") (pinfunction "2_2") (pintype "passive"))
      (node (ref "R40") (pin "2") (pinfunction "2_2") (pintype "passive"))
      (node (ref "U1") (pin "1") (pinfunction "A_1") (pintype "passive"))
      (node (ref "U3") (pin "2") (pintype "passive"))
      (node (ref "U3") (pin "4") (pintype "passive"))
      (node (ref "U6") (pin "16") (pinfunction "VCC_16") (pintype "passive"))
    )
    (net (code "42") (name "GND12") (class "Default")
      (node (ref "C5") (pin "2") (pinfunction "2_2") (pintype "passive"))
      (node (ref "C6") (pin "1") (pinfunction "1_1") (pintype "passive"))
      (node (ref "C7") (pin "2") (pinfunction "2_2") (pintype "passive"))
      (node (ref "D3") (pin "1") (pinfunction "A_1") (pintype "passive"))
      (node (ref "P1") (pin "2") (pinfunction "2_2") (pintype "passive"))
      (node (ref "Q1") (pin "2") (pinfunction "E_2") (pintype "passive"))
      (node (ref "R4") (pin "1") (pinfunction "1_1") (pintype "passive"))
      (node (ref "R5") (pin "1") (pinfunction "1_1") (pintype "passive"))
    )
    (net (code "43") (name "GNDA") (class "Default")
      (node (ref "C13") (pin "1") (pinfunction "1_1") (pintype "passive"))
      (node (ref "C15") (pin "2") (pinfunction "2_2") (pintype "passive"))
      (node (ref "C16") (pin "1") (pinfunction "1_1") (pintype "passive"))
      (node (ref "C20") (pin "1") (pinfunction "1_1") (pintype "passive"))
      (node (ref "C24") (pin "2") (pinfunction "2_2") (pintype "passive"))
      (node (ref "C33") (pin "1") (pinfunction "1_1") (pintype "passive"))
      (node (ref "C34") (pin "1") (pinfunction "1_1") (pintype "passive"))
      (node (ref "C37") (pin "1") (pinfunction "1_1") (pintype "passive"))
      (node (ref "C44") (pin "1") (pinfunction "1_1") (pintype "passive"))
      (node (ref "P2") (pin "7") (pinfunction "7_7") (pintype "passive"))
      (node (ref "P2") (pin "8") (pinfunction "8_8") (pintype "passive"))
      (node (ref "T8") (pin "1") (pinfunction "A_1") (pintype "passive"))
      (node (ref "U3") (pin "1") (pintype "passive"))
      (node (ref "U6") (pin "8") (pinfunction "GND_8") (pintype "passive"))
    )
    (net (code "44") (name "N15V+") (class "Default")
      (node (ref "D1") (pin "1") (pinfunction "A_1") (pintype "passive"))
    )
    (net (code "45") (name "N15V-") (class "Default")
      (node (ref "C17") (pin "2") (pinfunction "2_2") (pintype "passive"))
      (node (ref "C18") (pin "2") (pinfunction "2_2") (pintype "passive"))
      (node (ref "C19") (pin "2") (pinfunction "2_2") (pintype "passive"))
      (node (ref "C2") (pin "1") (pinfunction "1_1") (pintype "passive"))
      (node (ref "C22") (pin "2") (pinfunction "2_2") (pintype "passive"))
      (node (ref "C25") (pin "1") (pinfunction "1_1") (pintype "passive"))
      (node (ref "C3") (pin "2") (pinfunction "2_2") (pintype "passive"))
      (node (ref "C4") (pin "2") (pinfunction "2_2") (pintype "passive"))
      (node (ref "C8") (pin "2") (pinfunction "2_2") (pintype "passive"))
      (node (ref "C9") (pin "1") (pinfunction "1_1") (pintype "passive"))
      (node (ref "D10") (pin "3") (pinfunction "A_3") (pintype "passive"))
      (node (ref "D5") (pin "2") (pinfunction "K_2") (pintype "passive"))
      (node (ref "D6") (pin "3") (pinfunction "A_3") (pintype "passive"))
      (node (ref "D8") (pin "3") (pinfunction "A_3") (pintype "passive"))
      (node (ref "Q3") (pin "3") (pinfunction "E_3") (pintype "passive"))
      (node (ref "Q5") (pin "3") (pinfunction "E_3") (pintype "passive"))
      (node (ref "Q7") (pin "3") (pinfunction "E_3") (pintype "passive"))
      (node (ref "R13") (pin "1") (pinfunction "1_1") (pintype "passive"))
      (node (ref "R20") (pin "1") (pinfunction "1_1") (pintype "passive"))
      (node (ref "R22") (pin "1") (pinfunction "1_1") (pintype "passive"))
      (node (ref "R28") (pin "1") (pinfunction "1_1") (pintype "passive"))
      (node (ref "T1") (pin "1") (pinfunction "A_1") (pintype "passive"))
      (node (ref "T1") (pin "2") (pinfunction "2_2") (pintype "passive"))
      (node (ref "U2") (pin "2") (pinfunction "Vin-_2") (pintype "passive"))
      (node (ref "U2") (pin "8") (pinfunction "GND1_8") (pintype "passive"))
      (node (ref "VR1") (pin "2") (pinfunction "GND_2") (pintype "passive"))
    )
    (net (code "46") (name "Net-(CT1-IP-)") (class "Default")
      (node (ref "CT1") (pin "5") (pinfunction "IP-_5") (pintype "passive"))
      (node (ref "T10") (pin "1") (pinfunction "A_1") (pintype "passive"))
      (node (ref "T10") (pin "2") (pinfunction "2_2") (pintype "passive"))
    )
    (net (code "47") (name "Net-(CT1-VIOUT)") (class "Default")
      (node (ref "CT1") (pin "3") (pinfunction "VIOUT_3") (pintype "passive"))
      (node (ref "R36") (pin "1") (pinfunction "1_1") (pintype "passive"))
    )
    (net (code "48") (name "Net-(CT2-IP-)") (class "Default")
      (node (ref "CT2") (pin "5") (pinfunction "IP-_5") (pintype "passive"))
      (node (ref "T11") (pin "1") (pinfunction "A_1") (pintype "passive"))
      (node (ref "T11") (pin "2") (pinfunction "2_2") (pintype "passive"))
    )
    (net (code "49") (name "Net-(CT2-VIOUT)") (class "Default")
      (node (ref "CT2") (pin "3") (pinfunction "VIOUT_3") (pintype "passive"))
      (node (ref "R37") (pin "1") (pinfunction "1_1") (pintype "passive"))
    )
    (net (code "50") (name "Net-(CT3-IP-)") (class "Default")
      (node (ref "CT3") (pin "5") (pinfunction "IP-_5") (pintype "passive"))
      (node (ref "T12") (pin "1") (pinfunction "A_1") (pintype "passive"))
      (node (ref "T12") (pin "2") (pinfunction "2_2") (pintype "passive"))
    )
    (net (code "51") (name "Net-(CT3-VIOUT)") (class "Default")
      (node (ref "CT3") (pin "3") (pinfunction "VIOUT_3") (pintype "passive"))
      (node (ref "R38") (pin "1") (pinfunction "1_1") (pintype "passive"))
    )
    (net (code "52") (name "Net-(D1-K)") (class "Default")
      (node (ref "C2") (pin "2") (pinfunction "2_2") (pintype "passive"))
      (node (ref "D1") (pin "2") (pinfunction "K_2") (pintype "passive"))
      (node (ref "VR1") (pin "1") (pinfunction "Vin_1") (pintype "passive"))
    )
    (net (code "53") (name "Net-(D2-K)") (class "Default")
      (node (ref "D2") (pin "2") (pinfunction "K_2") (pintype "passive"))
      (node (ref "R5") (pin "2") (pinfunction "2_2") (pintype "passive"))
    )
    (net (code "54") (name "Net-(D3-K)") (class "Default")
      (node (ref "D3") (pin "2") (pinfunction "K_2") (pintype "passive"))
      (node (ref "R6") (pin "2") (pinfunction "2_2") (pintype "passive"))
    )
    (net (code "55") (name "Net-(D4-A)") (class "Default")
      (node (ref "D4") (pin "1") (pinfunction "A_1") (pintype "passive"))
      (node (ref "K1") (pin "3") (pinfunction "3_3") (pintype "passive"))
      (node (ref "Q1") (pin "3") (pinfunction "C_3") (pintype "passive"))
    )
    (net (code "56") (name "Net-(D5-A)") (class "Default")
      (node (ref "D5") (pin "1") (pinfunction "A_1") (pintype "passive"))
      (node (ref "R15") (pin "1") (pinfunction "1_1") (pintype "passive"))
    )
    (net (code "57") (name "Net-(D11-K)") (class "Default")
      (node (ref "D11") (pin "2") (pinfunction "K_2") (pintype "passive"))
      (node (ref "R26") (pin "1") (pinfunction "1_1") (pintype "passive"))
    )
    (net (code "58") (name "Net-(D12-K)") (class "Default")
      (node (ref "D12") (pin "2") (pinfunction "K_2") (pintype "passive"))
      (node (ref "R27") (pin "1") (pinfunction "1_1") (pintype "passive"))
    )
    (net (code "59") (name "Net-(D13-K)") (class "Default")
      (node (ref "C17") (pin "1") (pinfunction "1_1") (pintype "passive"))
      (node (ref "C18") (pin "1") (pinfunction "1_1") (pintype "passive"))
      (node (ref "C19") (pin "1") (pinfunction "1_1") (pintype "passive"))
      (node (ref "C22") (pin "1") (pinfunction "1_1") (pintype "passive"))
      (node (ref "C25") (pin "2") (pinfunction "2_2") (pintype "passive"))
      (node (ref "D13") (pin "1") (pinfunction "K_1") (pintype "passive"))
      (node (ref "D7") (pin "1") (pinfunction "K_1") (pintype "passive"))
      (node (ref "D9") (pin "1") (pinfunction "K_1") (pintype "passive"))
      (node (ref "K1") (pin "4") (pinfunction "4_4") (pintype "passive"))
      (node (ref "Q2") (pin "2") (pinfunction "C_2") (pintype "passive"))
      (node (ref "Q4") (pin "2") (pinfunction "C_2") (pintype "passive"))
      (node (ref "Q6") (pin "2") (pinfunction "C_2") (pintype "passive"))
      (node (ref "R10") (pin "2") (pinfunction "2_2") (pintype "passive"))
      (node (ref "R18") (pin "1") (pinfunction "1_1") (pintype "passive"))
      (node (ref "R7") (pin "1") (pinfunction "1_1") (pintype "passive"))
    )
    (net (code "60") (name "Net-(D14-A)") (class "Default")
      (node (ref "D14") (pin "1") (pinfunction "A_1") (pintype "passive"))
      (node (ref "R31") (pin "1") (pinfunction "1_1") (pintype "passive"))
    )
    (net (code "61") (name "Net-(D15-A)") (class "Default")
      (node (ref "D15") (pin "1") (pinfunction "A_1") (pintype "passive"))
      (node (ref "R32") (pin "1") (pinfunction "1_1") (pintype "passive"))
    )
    (net (code "62") (name "Net-(D16-K)") (class "Default")
      (node (ref "D16") (pin "2") (pinfunction "K_2") (pintype "passive"))
      (node (ref "R35") (pin "1") (pinfunction "1_1") (pintype "passive"))
    )
    (net (code "63") (name "Net-(D17-A)") (class "Default")
      (node (ref "D17") (pin "1") (pinfunction "A_1") (pintype "passive"))
      (node (ref "R40") (pin "1") (pinfunction "1_1") (pintype "passive"))
    )
    (net (code "64") (name "Net-(F1-Pad2)") (class "Default")
      (node (ref "F1") (pin "2") (pinfunction "2_2") (pintype "passive"))
      (node (ref "K1") (pin "1") (pinfunction "1_1") (pintype "passive"))
      (node (ref "R7") (pin "2") (pinfunction "2_2") (pintype "passive"))
    )
    (net (code "65") (name "Net-(Q1-B)") (class "Default")
      (node (ref "C6") (pin "2") (pinfunction "2_2") (pintype "passive"))
      (node (ref "Q1") (pin "1") (pinfunction "B_1") (pintype "passive"))
      (node (ref "R3") (pin "1") (pinfunction "1_1") (pintype "passive"))
      (node (ref "R4") (pin "2") (pinfunction "2_2") (pintype "passive"))
    )
    (net (code "66") (name "Net-(R10-Pad1)") (class "Default")
      (node (ref "R10") (pin "1") (pinfunction "1_1") (pintype "passive"))
      (node (ref "R11") (pin "2") (pinfunction "2_2") (pintype "passive"))
    )
    (net (code "67") (name "Net-(R11-Pad1)") (class "Default")
      (node (ref "R11") (pin "1") (pinfunction "1_1") (pintype "passive"))
      (node (ref "R12") (pin "2") (pinfunction "2_2") (pintype "passive"))
    )
    (net (code "68") (name "Net-(R14-Pad1)") (class "Default")
      (node (ref "R14") (pin "1") (pinfunction "1_1") (pintype "passive"))
      (node (ref "R15") (pin "2") (pinfunction "2_2") (pintype "passive"))
    )
    (net (code "69") (name "Net-(R14-Pad2)") (class "Default")
      (node (ref "R14") (pin "2") (pinfunction "2_2") (pintype "passive"))
      (node (ref "R16") (pin "2") (pinfunction "2_2") (pintype "passive"))
    )
    (net (code "70") (name "Net-(R16-Pad1)") (class "Default")
      (node (ref "R16") (pin "1") (pinfunction "1_1") (pintype "passive"))
      (node (ref "R17") (pin "2") (pinfunction "2_2") (pintype "passive"))
    )
    (net (code "71") (name "Net-(R17-Pad1)") (class "Default")
      (node (ref "R17") (pin "1") (pinfunction "1_1") (pintype "passive"))
      (node (ref "R18") (pin "2") (pinfunction "2_2") (pintype "passive"))
    )
    (net (code "72") (name "Net-(T2-A)") (class "Default")
      (node (ref "F1") (pin "1") (pinfunction "1_1") (pintype "passive"))
      (node (ref "T2") (pin "1") (pinfunction "A_1") (pintype "passive"))
      (node (ref "T2") (pin "2") (pinfunction "2_2") (pintype "passive"))
    )
    (net (code "73") (name "Net-(U1-E)") (class "Default")
      (node (ref "R3") (pin "2") (pinfunction "2_2") (pintype "passive"))
      (node (ref "U1") (pin "4") (pinfunction "E_4") (pintype "passive"))
    )
    (net (code "74") (name "Net-(U1-K)") (class "Default")
      (node (ref "R1") (pin "1") (pinfunction "1_1") (pintype "passive"))
      (node (ref "U1") (pin "3") (pinfunction "K_3") (pintype "passive"))
    )
    (net (code "75") (name "Net-(U2-ABSVAL)") (class "Default")
      (node (ref "R8") (pin "1") (pinfunction "1_1") (pintype "passive"))
      (node (ref "U2") (pin "13") (pinfunction "ABSVAL_13") (pintype "passive"))
    )
    (net (code "76") (name "Net-(U2-CH)") (class "Default")
      (node (ref "C1") (pin "2") (pinfunction "2_2") (pintype "passive"))
      (node (ref "U2") (pin "3") (pinfunction "CH_3") (pintype "passive"))
    )
    (net (code "77") (name "Net-(U2-CL)") (class "Default")
      (node (ref "C1") (pin "1") (pinfunction "1_1") (pintype "passive"))
      (node (ref "U2") (pin "4") (pinfunction "CL_4") (pintype "passive"))
    )
    (net (code "78") (name "Net-(U2-Vin+)") (class "Default")
      (node (ref "C4") (pin "1") (pinfunction "1_1") (pintype "passive"))
      (node (ref "R2") (pin "2") (pinfunction "2_2") (pintype "passive"))
      (node (ref "U2") (pin "1") (pinfunction "Vin+_1") (pintype "passive"))
    )
    (net (code "79") (name "Net-(U5A-IN-)") (class "Default")
      (node (ref "C29") (pin "2") (pinfunction "2_2") (pintype "passive"))
      (node (ref "C31") (pin "2") (pinfunction "2_2") (pintype "passive"))
      (node (ref "R102") (pin "2") (pinfunction "2_2") (pintype "passive"))
      (node (ref "R103") (pin "1") (pinfunction "1_1") (pintype "passive"))
      (node (ref "R26") (pin "2") (pinfunction "2_2") (pintype "passive"))
      (node (ref "U5") (pin "5") (pinfunction "IN-_5") (pintype "input"))
    )
    (net (code "80") (name "Net-(U5B-IN-)") (class "Default")
      (node (ref "C30") (pin "2") (pinfunction "2_2") (pintype "passive"))
      (node (ref "C32") (pin "2") (pinfunction "2_2") (pintype "passive"))
      (node (ref "R100") (pin "2") (pinfunction "2_2") (pintype "passive"))
      (node (ref "R101") (pin "1") (pinfunction "1_1") (pintype "passive"))
      (node (ref "R27") (pin "2") (pinfunction "2_2") (pintype "passive"))
      (node (ref "U5") (pin "7") (pinfunction "IN-_7") (pintype "input"))
    )
    (net (code "81") (name "Net-(U5C-IN-)") (class "Default")
      (node (ref "C35") (pin "2") (pinfunction "2_2") (pintype "passive"))
      (node (ref "C36") (pin "2") (pinfunction "2_2") (pintype "passive"))
      (node (ref "R104") (pin "2") (pinfunction "2_2") (pintype "passive"))
      (node (ref "R105") (pin "1") (pinfunction "1_1") (pintype "passive"))
      (node (ref "R35") (pin "2") (pinfunction "2_2") (pintype "passive"))
      (node (ref "U5") (pin "9") (pinfunction "IN-_9") (pintype "input"))
    )
    (net (code "82") (name "Net-(U6-~{MR})") (class "Default")
      (node (ref "R33") (pin "1") (pinfunction "1_1") (pintype "passive"))
      (node (ref "U6") (pin "1") (pinfunction "~{MR}_1") (pintype "passive"))
    )
    (net (code "83") (name "P_5V") (class "Default")
      (node (ref "C3") (pin "1") (pinfunction "1_1") (pintype "passive"))
      (node (ref "C8") (pin "1") (pinfunction "1_1") (pintype "passive"))
      (node (ref "C9") (pin "2") (pinfunction "2_2") (pintype "passive"))
      (node (ref "U2") (pin "5") (pinfunction "VDD1_5") (pintype "passive"))
      (node (ref "U2") (pin "7") (pinfunction "VDD1_7") (pintype "passive"))
      (node (ref "VR1") (pin "3") (pinfunction "Vout_3") (pintype "passive"))
    )
    (net (code "84") (name "unconnected-(K1-Pad5)") (class "Default")
      (node (ref "K1") (pin "5") (pinfunction "5_5") (pintype "passive+no_connect"))
    )
    (net (code "85") (name "unconnected-(U2-VLED+-Pad6)") (class "Default")
      (node (ref "U2") (pin "6") (pinfunction "VLED+_6") (pintype "passive+no_connect"))
    )
    (net (code "86") (name "unconnected-(U2-Vout-Pad12)") (class "Default")
      (node (ref "U2") (pin "12") (pinfunction "Vout_12") (pintype "passive+no_connect"))
    )
    (net (code "87") (name "unconnected-(U6-D3-Pad11)") (class "Default")
      (node (ref "U6") (pin "11") (pinfunction "D3_11") (pintype "passive+no_connect"))
    )
    (net (code "88") (name "unconnected-(U6-D4-Pad13)") (class "Default")
      (node (ref "U6") (pin "13") (pinfunction "D4_13") (pintype "passive+no_connect"))
    )
    (net (code "89") (name "unconnected-(U6-D5-Pad14)") (class "Default")
      (node (ref "U6") (pin "14") (pinfunction "D5_14") (pintype "passive+no_connect"))
    )
    (net (code "90") (name "unconnected-(U6-Q3-Pad10)") (class "Default")
      (node (ref "U6") (pin "10") (pinfunction "Q3_10") (pintype "passive+no_connect"))
    )
    (net (code "91") (name "unconnected-(U6-Q4-Pad12)") (class "Default")
      (node (ref "U6") (pin "12") (pinfunction "Q4_12") (pintype "passive+no_connect"))
    )
    (net (code "92") (name "unconnected-(U6-Q5-Pad15)") (class "Default")
      (node (ref "U6") (pin "15") (pinfunction "Q5_15") (pintype "passive+no_connect"))
    )
  )
)
